# Microphone-Boards_V1_0_GMA4030H11.net
KiCad netlist of a schematic drawn in Altium Designer
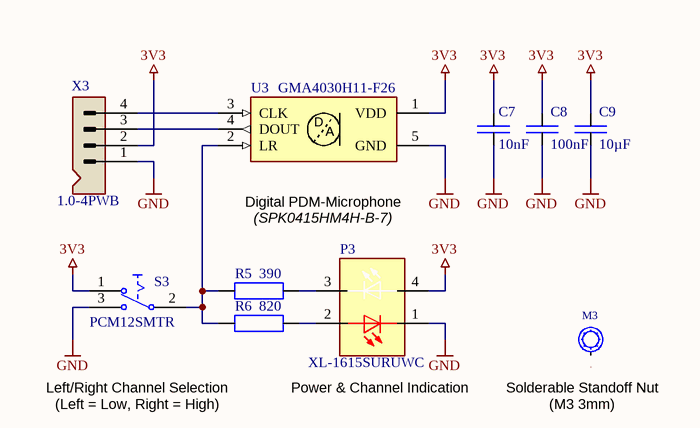
[diagram p0: Microphone-Boards_V1.0_GMA4030H11.SchDoc]

(export (version "E")
  (design (tool "Eeschema 10.0.6"))
  (components
    (comp (ref "C7")
      (value "10nF")
      (footprint "SMD Keramikkondensator 0603")
      (description "CAP-MK")
      (libsource (lib "AudioAmp") (part "C-CAPACITOR"))
    )
    (comp (ref "C8")
      (value "100nF")
      (footprint "SMD Keramikkondensator 0603")
      (description "SMD Ceramic Capacitor E6")
      (libsource (lib "Ceramic Capacitors-E6") (part "E6 - 100nF"))
    )
    (comp (ref "C9")
      (value "10µF")
      (footprint "SMD Keramikkondensator 1206")
      (description "SMD Ceramic Capacitor E6")
      (libsource (lib "Ceramic Capacitors-E6") (part "E6 - 10uF"))
    )
    (comp (ref "M3")
      (value "SMTSO-M3-3ET")
      (footprint "SMD Solder-Nut (M3 3mm)")
      (description "Solderable Standoff Nut")
      (libsource (lib "Velotour_2022") (part "M-Spacer_M3_3mm"))
    )
    (comp (ref "P3")
      (value "XL-1615SURUWC")
      (footprint "SMD LED 0606")
      (description "LED Red/White")
      (libsource (lib "Microphone-Boards") (part "P-XL-1615SURUWC"))
    )
    (comp (ref "R5")
      (value "390")
      (footprint "SMD Widerstand 0603")
      (description "SMD-Widerstand 1/4W")
      (libsource (lib "Backplane_1") (part "R-RESISTOR"))
    )
    (comp (ref "R6")
      (value "820")
      (footprint "SMD Widerstand 0603")
      (description "SMD-Widerstand 1/4W")
      (libsource (lib "Backplane_1") (part "R-RESISTOR"))
    )
    (comp (ref "S3")
      (value "PCM12SMTR")
      (footprint "SMD Switch SPDT (PCM12SMTR)")
      (description "Miniature Slide Switch")
      (libsource (lib "Custom ST-Link") (part "S-PCM12SMTR"))
    )
    (comp (ref "U3")
      (value "GMA4030H11-F26")
      (footprint "SMD Microphone (GMA4030H11-F26)")
      (description "Digital PDM MEMS Microphone (Top Port)")
      (libsource (lib "Microphone-Boards") (part "U-GMA4030H11-F26"))
    )
    (comp (ref "X3")
      (value "1.0-4PWB")
      (footprint "SMD Connector (SM04B-SRSS-TB)")
      (description "Wire To Board Connector (1x4P 1.0mm)")
      (libsource (lib "Audio-Beamformer") (part "X-Stiftleiste (4-Fach)"))
    )
  )
  (nets
    (net (code "1") (name "/M") (class "Default")
      (node (ref "M3") (pin "1") (pinfunction "1_1") (pintype "passive"))
    )
    (net (code "2") (name "3V3") (class "Default")
      (node (ref "C7") (pin "2") (pinfunction "2_2") (pintype "passive"))
      (node (ref "C8") (pin "2") (pinfunction "2_2") (pintype "passive"))
      (node (ref "C9") (pin "2") (pinfunction "2_2") (pintype "passive"))
      (node (ref "P3") (pin "4") (pinfunction "WA_4") (pintype "passive"))
      (node (ref "S3") (pin "1") (pinfunction "NC1_1") (pintype "passive"))
      (node (ref "U3") (pin "1") (pinfunction "VDD_1") (pintype "power_in"))
      (node (ref "X3") (pin "2") (pinfunction "2_2") (pintype "passive"))
    )
    (net (code "3") (name "GND") (class "Default")
      (node (ref "C7") (pin "1") (pinfunction "1_1") (pintype "passive"))
      (node (ref "C8") (pin "1") (pinfunction "1_1") (pintype "passive"))
      (node (ref "C9") (pin "1") (pinfunction "1_1") (pintype "passive"))
      (node (ref "P3") (pin "1") (pinfunction "RC_1") (pintype "passive"))
      (node (ref "S3") (pin "3") (pinfunction "NO1_3") (pintype "passive"))
      (node (ref "U3") (pin "5") (pinfunction "GND_5") (pintype "power_in"))
      (node (ref "X3") (pin "1") (pinfunction "1_1") (pintype "passive"))
    )
    (net (code "4") (name "Net-(P3-RA)") (class "Default")
      (node (ref "P3") (pin "2") (pinfunction "RA_2") (pintype "passive"))
      (node (ref "R6") (pin "2") (pinfunction "2_2") (pintype "passive"))
    )
    (net (code "5") (name "Net-(P3-WC)") (class "Default")
      (node (ref "P3") (pin "3") (pinfunction "WC_3") (pintype "passive"))
      (node (ref "R5") (pin "2") (pinfunction "2_2") (pintype "passive"))
    )
    (net (code "6") (name "Net-(S3-COMMON1)") (class "Default")
      (node (ref "R5") (pin "1") (pinfunction "1_1") (pintype "passive"))
      (node (ref "R6") (pin "1") (pinfunction "1_1") (pintype "passive"))
      (node (ref "S3") (pin "2") (pinfunction "COMMON1_2") (pintype "passive"))
      (node (ref "U3") (pin "2") (pinfunction "LR_2") (pintype "input"))
    )
    (net (code "7") (name "Net-(U3-CLK)") (class "Default")
      (node (ref "U3") (pin "3") (pinfunction "CLK_3") (pintype "input"))
      (node (ref "X3") (pin "4") (pinfunction "4_4") (pintype "passive"))
    )
    (net (code "8") (name "Net-(U3-DOUT)") (class "Default")
      (node (ref "U3") (pin "4") (pinfunction "DOUT_4") (pintype "output"))
      (node (ref "X3") (pin "3") (pinfunction "3_3") (pintype "passive"))
    )
  )
)
